# walktimizer_v2.net
KiCad netlist of a schematic drawn in Altium Designer
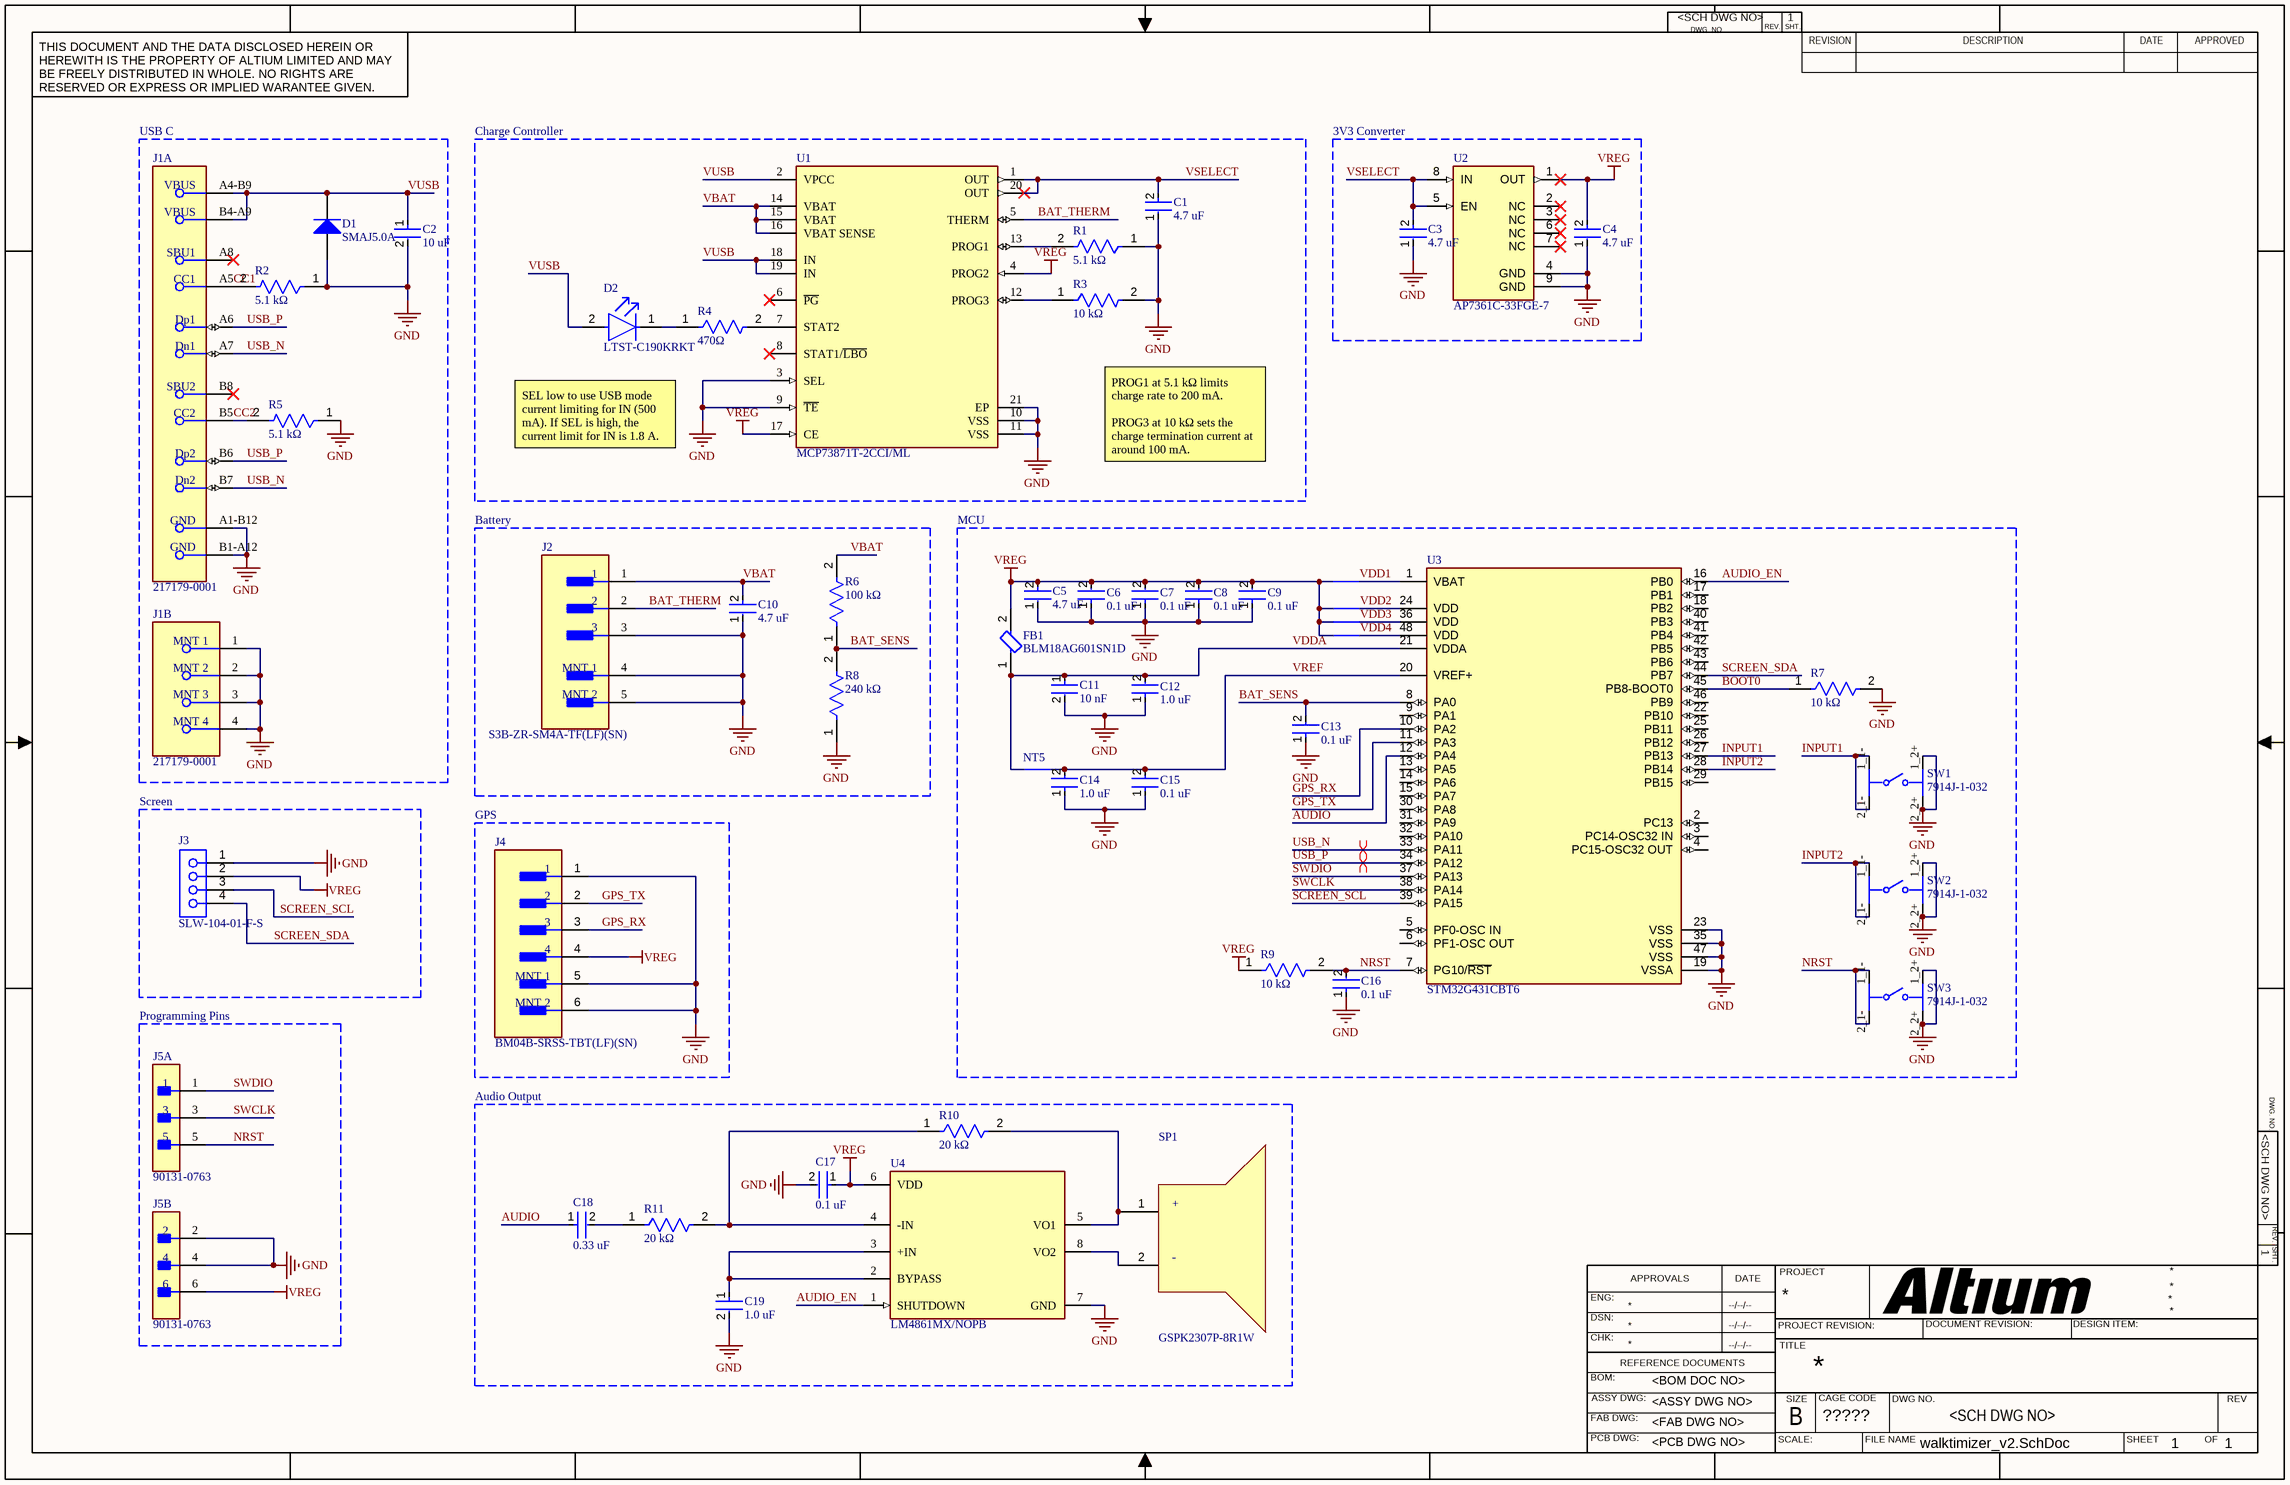
[diagram p0: walktimizer_v2.SchDoc]

(export (version "E")
  (design (tool "Eeschema 10.0.6"))
  (components
    (comp (ref "C1")
      (value "4.7 uF")
      (footprint "FP-GRM188-0_1-MFG")
      (description "CAP CER 4.7UF 6.3V X5R 0603\r\n\r\nGRM188R60J475KE19D")
      (fields (field (name "VOLTAGE") "6.3V") (field (name "TOLERANCE") "10%"))
      (libsource (lib "Altium Content Vault") (part "236180d848d6139a670b325ea6854c9"))
    )
    (comp (ref "C2")
      (value "10 uF")
      (footprint "FP-GRM21B-0_2-e0_2_0_7-IPC_A")
      (fields (field (name "TOLERANCE") "10%"))
      (libsource (lib "Altium Content Vault") (part "b4654b650e69147ec39a6b967a45e02"))
    )
    (comp (ref "C3")
      (value "4.7 uF")
      (footprint "FP-GRM188-0_1-MFG")
      (description "CAP CER 4.7UF 6.3V X5R 0603\r\n\r\nGRM188R60J475KE19D")
      (fields (field (name "VOLTAGE") "6.3V") (field (name "TOLERANCE") "10%"))
      (libsource (lib "Altium Content Vault") (part "236180d848d6139a670b325ea6854c9"))
    )
    (comp (ref "C4")
      (value "4.7 uF")
      (footprint "FP-GRM188-0_1-MFG")
      (description "CAP CER 4.7UF 6.3V X5R 0603\r\n\r\nGRM188R60J475KE19D")
      (fields (field (name "VOLTAGE") "6.3V") (field (name "TOLERANCE") "10%"))
      (libsource (lib "Altium Content Vault") (part "236180d848d6139a670b325ea6854c9"))
    )
    (comp (ref "C5")
      (value "4.7 uF")
      (footprint "FP-GRM188-0_1-MFG")
      (description "CAP CER 4.7UF 6.3V X5R 0603\r\n\r\nGRM188R60J475KE19D")
      (fields (field (name "VOLTAGE") "6.3V") (field (name "TOLERANCE") "10%"))
      (libsource (lib "Altium Content Vault") (part "236180d848d6139a670b325ea6854c9"))
    )
    (comp (ref "C6")
      (value "0.1 uF")
      (footprint "FP-CC0603-DA-MFG")
      (description "CAP CER 0.1UF 50V X7R 0603\r\n\r\nCC0603KRX7R9BB104")
      (fields (field (name "MANUFACTURER") "YAGEO") (field (name "VOLTAGE") "50 V"))
      (libsource (lib "Altium Content Vault") (part "11868f565c42a9108669ba33697ecf6"))
    )
    (comp (ref "C7")
      (value "0.1 uF")
      (footprint "FP-CC0603-DA-MFG")
      (description "CAP CER 0.1UF 50V X7R 0603\r\n\r\nCC0603KRX7R9BB104")
      (fields (field (name "MANUFACTURER") "YAGEO") (field (name "VOLTAGE") "50 V"))
      (libsource (lib "Altium Content Vault") (part "11868f565c42a9108669ba33697ecf6"))
    )
    (comp (ref "C8")
      (value "0.1 uF")
      (footprint "FP-CC0603-DA-MFG")
      (description "CAP CER 0.1UF 50V X7R 0603\r\n\r\nCC0603KRX7R9BB104")
      (fields (field (name "MANUFACTURER") "YAGEO") (field (name "VOLTAGE") "50 V"))
      (libsource (lib "Altium Content Vault") (part "11868f565c42a9108669ba33697ecf6"))
    )
    (comp (ref "C9")
      (value "0.1 uF")
      (footprint "FP-CC0603-DA-MFG")
      (description "CAP CER 0.1UF 50V X7R 0603\r\n\r\nCC0603KRX7R9BB104")
      (fields (field (name "MANUFACTURER") "YAGEO") (field (name "VOLTAGE") "50 V"))
      (libsource (lib "Altium Content Vault") (part "11868f565c42a9108669ba33697ecf6"))
    )
    (comp (ref "C10")
      (value "4.7 uF")
      (footprint "FP-GRM188-0_1-MFG")
      (description "CAP CER 4.7UF 6.3V X5R 0603\r\n\r\nGRM188R60J475KE19D")
      (fields (field (name "VOLTAGE") "6.3V") (field (name "TOLERANCE") "10%"))
      (libsource (lib "Altium Content Vault") (part "236180d848d6139a670b325ea6854c9"))
    )
    (comp (ref "C11")
      (value "10 nF")
      (footprint "FP-CC0603-DA-MFG")
      (description "CAP CER 10000PF 50V X7R 0603\r\n\r\nCC0603KRX7R9BB103")
      (fields (field (name "TOLERANCE") "0.1") (field (name "MANUFACTURER PART NUMBER") "CC0603KRX7R9BB103"))
      (libsource (lib "Altium Content Vault") (part "11868f565c42a9108669ba33697ecf6"))
    )
    (comp (ref "C12")
      (value "1.0 uF")
      (footprint "FP-CC0603-DB-MFG")
      (description "CAP CER 1UF 50V X7R 0603\r\n\r\nCC0603KRX7R9BB105")
      (fields (field (name "TOLERANCE") "10%"))
      (libsource (lib "Altium Content Vault") (part "11868f565c42a9108669ba33697ecf6"))
    )
    (comp (ref "C13")
      (value "0.1 uF")
      (footprint "FP-CC0603-DA-MFG")
      (description "CAP CER 0.1UF 50V X7R 0603\r\n\r\nCC0603KRX7R9BB104")
      (fields (field (name "MANUFACTURER") "YAGEO") (field (name "VOLTAGE") "50 V"))
      (libsource (lib "Altium Content Vault") (part "11868f565c42a9108669ba33697ecf6"))
    )
    (comp (ref "C14")
      (value "1.0 uF")
      (footprint "FP-CC0603-DB-MFG")
      (description "CAP CER 1UF 50V X7R 0603\r\n\r\nCC0603KRX7R9BB105")
      (fields (field (name "TOLERANCE") "10%"))
      (libsource (lib "Altium Content Vault") (part "11868f565c42a9108669ba33697ecf6"))
    )
    (comp (ref "C15")
      (value "0.1 uF")
      (footprint "FP-CC0603-DA-MFG")
      (description "CAP CER 0.1UF 50V X7R 0603\r\n\r\nCC0603KRX7R9BB104")
      (fields (field (name "MANUFACTURER") "YAGEO") (field (name "VOLTAGE") "50 V"))
      (libsource (lib "Altium Content Vault") (part "11868f565c42a9108669ba33697ecf6"))
    )
    (comp (ref "C16")
      (value "0.1 uF")
      (footprint "FP-CC0603-DA-MFG")
      (description "CAP CER 0.1UF 50V X7R 0603\r\n\r\nCC0603KRX7R9BB104")
      (fields (field (name "MANUFACTURER") "YAGEO") (field (name "VOLTAGE") "50 V"))
      (libsource (lib "Altium Content Vault") (part "11868f565c42a9108669ba33697ecf6"))
    )
    (comp (ref "C17")
      (value "0.1 uF")
      (footprint "FP-CC0603-DA-MFG")
      (description "CAP CER 0.1UF 50V X7R 0603\r\n\r\nCC0603KRX7R9BB104")
      (fields (field (name "MANUFACTURER") "YAGEO") (field (name "VOLTAGE") "50 V"))
      (libsource (lib "Altium Content Vault") (part "11868f565c42a9108669ba33697ecf6"))
    )
    (comp (ref "C18")
      (value "0.33 uF")
      (footprint "FP-CC0603-DA-MFG")
      (description "CAP CER 0.33UF 25V X7R 0603\r\n\r\nCC0603KRX7R8BB334")
      (fields
        (field (name "VOLTAGE") "25 V")
        (field (name "OCTOPART") "https://octopart.com/cc0603krx7r8bb334-yageo-47255252")
      )
      (libsource (lib "Altium Content Vault") (part "11868f565c42a9108669ba33697ecf6"))
    )
    (comp (ref "C19")
      (value "1.0 uF")
      (footprint "FP-CC0603-DB-MFG")
      (description "CAP CER 1UF 50V X7R 0603\r\n\r\nCC0603KRX7R9BB105")
      (fields (field (name "TOLERANCE") "10%"))
      (libsource (lib "Altium Content Vault") (part "11868f565c42a9108669ba33697ecf6"))
    )
    (comp (ref "D1")
      (value "SMAJ5.0A")
      (footprint "BOUR-SMA-2_V")
      (fields (field (name "MANUFACTURER") "Bourns"))
      (libsource (lib "Altium Content Vault") (part "D-AK-2"))
    )
    (comp (ref "D2")
      (value "LTST-C190KRKT")
      (footprint "FP-LTST-C190KRKT-MFG")
      (description "LED RED CLEAR CHIP SMD")
      (libsource (lib "Altium Content Vault") (part "8706943c75ba83719d021d2fdc84c58"))
    )
    (comp (ref "FB1")
      (value "BLM18AG601SN1D")
      (footprint "FP-BLM18-0_15-t0_8-MFG")
      (description "Chip Ferrite Bead, 0603, 600Ω @ 100MHz, 0.38Ω, 25%, 500mA")
      (fields (field (name "TOLERANCE") "25%"))
      (libsource (lib "Altium Content Vault") (part "5f30dd21d616792df468990f7003faa"))
    )
    (comp (ref "J1")
      (value "217179-0001")
      (footprint "FP-2171790001-MFG")
      (description "CONN RCP USB2.0 TYP C 24P SMD RA")
      (libsource (lib "Altium Content Vault") (part "8b86497a633d14b3f74642136fc0ce6"))
    )
    (comp (ref "J2")
      (value "S3B-ZR-SM4A-TF(LF)(SN)")
      (footprint "FP-S3B-ZR-SM4A-TF_LF_SN-MFG")
      (description "CONN HEADER SMD R/A 3POS 1.5MM")
      (libsource (lib "Altium Content Vault") (part "38689d6f3df0f9b234c6ddcef280d85"))
    )
    (comp (ref "J3")
      (value "SLW-104-01-F-S")
      (footprint "SMTC-SLW-104-01-X-S")
      (fields (field (name "MANUFACTURER") "Samtec"))
      (libsource (lib "Altium Content Vault") (part "SMTC-SLW-104-01-X-S"))
    )
    (comp (ref "J4")
      (value "BM04B-SRSS-TBT(LF)(SN)")
      (footprint "FP-BM04B-SRSS-TBT_LF_SN-MFG")
      (description "CONN HEADER SMD 4POS 1MM")
      (libsource (lib "Altium Content Vault") (part "8e3688c4b118bffc0dd9b7401e414ba"))
    )
    (comp (ref "J5")
      (value "90131-0763")
      (footprint "FP-90131-0763-MFG")
      (description "90131-0763 Conn Unshrouded Header HDR 6 POS 2.54mm Solder ST Top Entry Thru-Hole C-Grid III™ Tray")
      (libsource (lib "Altium Content Vault") (part "2654a11fb13586ecb194516b1c997bc"))
    )
    (comp (ref "NT1")
      (value "NT")
      (footprint "NETTIE_SMD")
      (description "Net Tie SMD")
      (libsource (lib "Schlib1") (part "NetTie_SMD"))
    )
    (comp (ref "NT2")
      (value "NT")
      (footprint "NETTIE_SMD")
      (description "Net Tie SMD")
      (libsource (lib "Schlib1") (part "NetTie_SMD"))
    )
    (comp (ref "NT3")
      (value "NT")
      (footprint "NETTIE_SMD")
      (description "Net Tie SMD")
      (libsource (lib "Schlib1") (part "NetTie_SMD"))
    )
    (comp (ref "NT4")
      (value "NT")
      (footprint "NETTIE_SMD")
      (description "Net Tie SMD")
      (libsource (lib "Schlib1") (part "NetTie_SMD"))
    )
    (comp (ref "NT5")
      (value "NT")
      (footprint "NETTIE_SMD")
      (description "Net Tie SMD")
      (libsource (lib "Schlib1") (part "NetTie_SMD"))
    )
    (comp (ref "R1")
      (value "5.1 kΩ")
      (footprint "FP-CRCW0603-e3-IPC_C")
      (description "RES Thick Film, 5.1kΩ, 1%, 0.1W, 100ppm/°C, 0603\r\n\r\nCRCW06035K10FKEA")
      (fields (field (name "TOLERANCE") "1%"))
      (libsource (lib "Altium Content Vault") (part "1029c3af85768c4190bb7ad29bc67b5"))
    )
    (comp (ref "R2")
      (value "5.1 kΩ")
      (footprint "FP-CRCW0603-e3-IPC_C")
      (description "RES Thick Film, 5.1kΩ, 1%, 0.1W, 100ppm/°C, 0603\r\n\r\nCRCW06035K10FKEA")
      (fields (field (name "TOLERANCE") "1%"))
      (libsource (lib "Altium Content Vault") (part "1029c3af85768c4190bb7ad29bc67b5"))
    )
    (comp (ref "R3")
      (value "10 kΩ")
      (footprint "FP-RC0603-0_55-IPC_C")
      (description "RES 10kΩ 1% 1/10W 0603\r\n\r\nRC0603FR-0710KL")
      (fields (field (name "TOLERANCE") "1%"))
      (libsource (lib "Altium Content Vault") (part "1029c3af85768c4190bb7ad29bc67b5"))
    )
    (comp (ref "R4")
      (value "470Ω")
      (footprint "FP-CRCW0603-e3-MFG")
      (description "RES Thick Film, 470Ω, 1%, 0.1W, 100ppm/°C, 0603\r\n\r\nCRCW0603470RFKEA")
      (fields (field (name "TOLERANCE") "1%"))
      (libsource (lib "Altium Content Vault") (part "1029c3af85768c4190bb7ad29bc67b5"))
    )
    (comp (ref "R5")
      (value "5.1 kΩ")
      (footprint "FP-CRCW0603-e3-IPC_C")
      (description "RES Thick Film, 5.1kΩ, 1%, 0.1W, 100ppm/°C, 0603\r\n\r\nCRCW06035K10FKEA")
      (fields (field (name "TOLERANCE") "1%"))
      (libsource (lib "Altium Content Vault") (part "1029c3af85768c4190bb7ad29bc67b5"))
    )
    (comp (ref "R6")
      (value "100 kΩ")
      (footprint "FP-RC0603-0_55-MFG")
      (description "RES SMD 100K OHM 1% 1/10W 0603\r\n\r\nRC0603FR-07100KL")
      (fields (field (name "TOLERANCE") "1%"))
      (libsource (lib "Altium Content Vault") (part "1029c3af85768c4190bb7ad29bc67b5"))
    )
    (comp (ref "R7")
      (value "10 kΩ")
      (footprint "FP-RC0603-0_55-IPC_C")
      (description "RES 10kΩ 1% 1/10W 0603\r\n\r\nRC0603FR-0710KL")
      (fields (field (name "TOLERANCE") "1%"))
      (libsource (lib "Altium Content Vault") (part "1029c3af85768c4190bb7ad29bc67b5"))
    )
    (comp (ref "R8")
      (value "240 kΩ")
      (footprint "FP-RT0603-MFG")
      (description "RES 240K OHM 1/10W .1% SMD 0603\r\n\r\nRT0603BRD07240KL")
      (fields
        (field (name "OCTOPART") "https://octopart.com/rt0603brd07240kl-yageo-1283207")
        (field (name "TOLERANCE") "0.001")
      )
      (libsource (lib "Altium Content Vault") (part "1029c3af85768c4190bb7ad29bc67b5"))
    )
    (comp (ref "R9")
      (value "10 kΩ")
      (footprint "FP-RC0603-0_55-IPC_C")
      (description "RES 10kΩ 1% 1/10W 0603\r\n\r\nRC0603FR-0710KL")
      (fields (field (name "TOLERANCE") "1%"))
      (libsource (lib "Altium Content Vault") (part "1029c3af85768c4190bb7ad29bc67b5"))
    )
    (comp (ref "R10")
      (value "20 kΩ")
      (footprint "FP-RC0603-0_55-IPC_C")
      (description "RES 20K OHM 1% 1/10W 0603\r\n\r\nRC0603FR-0720KL")
      (fields (field (name "TOLERANCE") "1%"))
      (libsource (lib "Altium Content Vault") (part "1029c3af85768c4190bb7ad29bc67b5"))
    )
    (comp (ref "R11")
      (value "20 kΩ")
      (footprint "FP-RC0603-0_55-IPC_C")
      (description "RES 20K OHM 1% 1/10W 0603\r\n\r\nRC0603FR-0720KL")
      (fields (field (name "TOLERANCE") "1%"))
      (libsource (lib "Altium Content Vault") (part "1029c3af85768c4190bb7ad29bc67b5"))
    )
    (comp (ref "SP1")
      (value "GSPK2307P-8R1W")
      (footprint "GSPK2307P-8R1W-Footprint-1")
      (description "8 ohm 1.7kHz Speakers ROHS 88dB 500 mW")
      (libsource (lib "Americas - University of Calgary - Schulich Unmanned Aerial Vehicle (SUAV)") (part "GSPK2307P-8R1W-Symbol-1"))
    )
    (comp (ref "SW1")
      (value "7914J-1-032")
      (footprint "FP-7914J-1-032-MFG")
      (description "SWITCH TACTILE SPST-NO 0.1A 16V")
      (libsource (lib "Altium Content Vault") (part "31b61e1575766857d5d37af9ed38f2e"))
    )
    (comp (ref "SW2")
      (value "7914J-1-032")
      (footprint "FP-7914J-1-032-MFG")
      (description "SWITCH TACTILE SPST-NO 0.1A 16V")
      (libsource (lib "Altium Content Vault") (part "31b61e1575766857d5d37af9ed38f2e"))
    )
    (comp (ref "SW3")
      (value "7914J-1-032")
      (footprint "FP-7914J-1-032-MFG")
      (description "SWITCH TACTILE SPST-NO 0.1A 16V")
      (libsource (lib "Altium Content Vault") (part "31b61e1575766857d5d37af9ed38f2e"))
    )
    (comp (ref "U1")
      (value "MCP73871T-2CCI/ML")
      (footprint "FP-C04-126-IPC_C")
      (description "IC USB/AC BATT CHRGR W/PPM 20QFN")
      (libsource (lib "Altium Content Vault") (part "b0f216601a400a2976e0698385bc2c7"))
    )
    (comp (ref "U2")
      (value "AP7361C-33FGE-7")
      (footprint "FP-U-DFN3030-8_Type_E-MFG")
      (description "IC REG LINEAR 3.3V 1A UDFN3030-8")
      (fields
        (field (name "MANUFACTURER") "Diodes Inc.")
        (field (name "OCTOPART") "https://octopart.com/ap7361c-33fge-7-diodes+inc.-65869522")
      )
      (libsource (lib "Altium Content Vault") (part "2971fe8480f7e8815ea3c3920f93e3e"))
    )
    (comp (ref "U3")
      (value "STM32G431CBT6")
      (footprint "FP-LQFP48-5B-MFG")
      (description "MAINSTREAM ARM CORTEX-M4+ MCU 17")
      (fields
        (field (name "MANUFACTURER") "STMicroelectronics")
        (field (name "OCTOPART") "https://octopart.com/stm32g431cbt6-stmicroelectronics-98835224")
      )
      (libsource (lib "Altium Content Vault") (part "08b09c1d51ec08ade740842f2b8671b"))
    )
    (comp (ref "U4")
      (value "LM4861MX/NOPB")
      (footprint "FP-D0008A-MFG")
      (description "IC AMP CLASS AB MONO 1.5W 8SOIC")
      (libsource (lib "Altium Content Vault") (part "2ffc3cc6e4eb487d9499d4bad086ba9"))
    )
  )
  (nets
    (net (code "1") (name "/AUDIO") (class "Default")
      (node (ref "C18") (pin "1") (pinfunction "1_1") (pintype "passive"))
      (node (ref "U3") (pin "12") (pinfunction "PA4_12") (pintype "bidirectional"))
    )
    (net (code "2") (name "/AUDIO_EN") (class "Default")
      (node (ref "U3") (pin "16") (pinfunction "PB0_16") (pintype "bidirectional"))
      (node (ref "U4") (pin "1") (pinfunction "SHUTDOWN_1") (pintype "input"))
    )
    (net (code "3") (name "/BAT_SENS") (class "Default")
      (node (ref "C13") (pin "2") (pinfunction "2_2") (pintype "passive"))
      (node (ref "R6") (pin "1") (pinfunction "1_1") (pintype "passive"))
      (node (ref "R8") (pin "2") (pinfunction "2_2") (pintype "passive"))
      (node (ref "U3") (pin "8") (pinfunction "PA0_8") (pintype "bidirectional"))
    )
    (net (code "4") (name "/BAT_THERM") (class "Default")
      (node (ref "J2") (pin "2") (pinfunction "2_2") (pintype "passive"))
      (node (ref "U1") (pin "5") (pinfunction "THERM_5") (pintype "bidirectional"))
    )
    (net (code "5") (name "/BOOT0") (class "Default")
      (node (ref "R7") (pin "1") (pinfunction "1_1") (pintype "passive"))
      (node (ref "U3") (pin "45") (pinfunction "PB8-BOOT0_45") (pintype "bidirectional"))
    )
    (net (code "6") (name "/CC1") (class "Default")
      (node (ref "J1") (pin "A5") (pinfunction "CC1_A5") (pintype "passive"))
      (node (ref "R2") (pin "2") (pinfunction "2_2") (pintype "passive"))
    )
    (net (code "7") (name "/CC2") (class "Default")
      (node (ref "J1") (pin "B5") (pinfunction "CC2_B5") (pintype "passive"))
      (node (ref "R5") (pin "2") (pinfunction "2_2") (pintype "passive"))
    )
    (net (code "8") (name "/GPS_RX") (class "Default")
      (node (ref "J4") (pin "3") (pinfunction "3_3") (pintype "passive"))
      (node (ref "U3") (pin "10") (pinfunction "PA2_10") (pintype "bidirectional"))
    )
    (net (code "9") (name "/GPS_TX") (class "Default")
      (node (ref "J4") (pin "2") (pinfunction "2_2") (pintype "passive"))
      (node (ref "U3") (pin "11") (pinfunction "PA3_11") (pintype "bidirectional"))
    )
    (net (code "10") (name "/INPUT1") (class "Default")
      (node (ref "SW1") (pin "1_1-") (pinfunction "1_1-_1_1-") (pintype "passive"))
      (node (ref "SW1") (pin "2_1-") (pinfunction "2_1-_2_1-") (pintype "passive"))
      (node (ref "U3") (pin "27") (pinfunction "PB13_27") (pintype "bidirectional"))
    )
    (net (code "11") (name "/INPUT2") (class "Default")
      (node (ref "SW2") (pin "1_1-") (pinfunction "1_1-_1_1-") (pintype "passive"))
      (node (ref "SW2") (pin "2_1-") (pinfunction "2_1-_2_1-") (pintype "passive"))
      (node (ref "U3") (pin "28") (pinfunction "PB14_28") (pintype "bidirectional"))
    )
    (net (code "12") (name "/NRST") (class "Default")
      (node (ref "C16") (pin "2") (pinfunction "2_2") (pintype "passive"))
      (node (ref "J5") (pin "5") (pinfunction "5_5") (pintype "passive"))
      (node (ref "R9") (pin "2") (pinfunction "2_2") (pintype "passive"))
      (node (ref "SW3") (pin "1_1-") (pinfunction "1_1-_1_1-") (pintype "passive"))
      (node (ref "SW3") (pin "2_1-") (pinfunction "2_1-_2_1-") (pintype "passive"))
      (node (ref "U3") (pin "7") (pinfunction "PG10/~{RST}_7") (pintype "bidirectional"))
    )
    (net (code "13") (name "/SCREEN_SCL") (class "Default")
      (node (ref "J3") (pin "3") (pinfunction "3_3") (pintype "passive"))
      (node (ref "U3") (pin "39") (pinfunction "PA15_39") (pintype "bidirectional"))
    )
    (net (code "14") (name "/SCREEN_SDA") (class "Default")
      (node (ref "J3") (pin "4") (pinfunction "4_4") (pintype "passive"))
      (node (ref "U3") (pin "44") (pinfunction "PB7_44") (pintype "bidirectional"))
    )
    (net (code "15") (name "/SWCLK") (class "Default")
      (node (ref "J5") (pin "3") (pinfunction "3_3") (pintype "passive"))
      (node (ref "U3") (pin "38") (pinfunction "PA14_38") (pintype "bidirectional"))
    )
    (net (code "16") (name "/SWDIO") (class "Default")
      (node (ref "J5") (pin "1") (pinfunction "1_1") (pintype "passive"))
      (node (ref "U3") (pin "37") (pinfunction "PA13_37") (pintype "bidirectional"))
    )
    (net (code "17") (name "/USB_N") (class "Default")
      (node (ref "J1") (pin "A7") (pinfunction "Dn1_A7") (pintype "bidirectional"))
      (node (ref "J1") (pin "B7") (pinfunction "Dn2_B7") (pintype "bidirectional"))
      (node (ref "U3") (pin "33") (pinfunction "PA11_33") (pintype "bidirectional"))
    )
    (net (code "18") (name "/USB_P") (class "Default")
      (node (ref "J1") (pin "A6") (pinfunction "Dp1_A6") (pintype "bidirectional"))
      (node (ref "J1") (pin "B6") (pinfunction "Dp2_B6") (pintype "bidirectional"))
      (node (ref "U3") (pin "34") (pinfunction "PA12_34") (pintype "bidirectional"))
    )
    (net (code "19") (name "/VBAT") (class "Default")
      (node (ref "C10") (pin "2") (pinfunction "2_2") (pintype "passive"))
      (node (ref "J2") (pin "1") (pinfunction "1_1") (pintype "passive"))
      (node (ref "R6") (pin "2") (pinfunction "2_2") (pintype "passive"))
      (node (ref "U1") (pin "14") (pinfunction "VBAT_14") (pintype "power_in"))
      (node (ref "U1") (pin "15") (pinfunction "VBAT_15") (pintype "power_in"))
      (node (ref "U1") (pin "16") (pinfunction "VBAT_SENSE_16") (pintype "power_in"))
    )
    (net (code "20") (name "/VDD1") (class "Default")
      (node (ref "NT1") (pin "2") (pinfunction "2_2") (pintype "passive"))
      (node (ref "U3") (pin "1") (pinfunction "VBAT_1") (pintype "power_in"))
    )
    (net (code "21") (name "/VDD2") (class "Default")
      (node (ref "NT2") (pin "2") (pinfunction "2_2") (pintype "passive"))
      (node (ref "U3") (pin "24") (pinfunction "VDD_24") (pintype "power_in"))
    )
    (net (code "22") (name "/VDD3") (class "Default")
      (node (ref "NT3") (pin "2") (pinfunction "2_2") (pintype "passive"))
      (node (ref "U3") (pin "36") (pinfunction "VDD_36") (pintype "power_in"))
    )
    (net (code "23") (name "/VDD4") (class "Default")
      (node (ref "NT4") (pin "2") (pinfunction "2_2") (pintype "passive"))
      (node (ref "U3") (pin "48") (pinfunction "VDD_48") (pintype "power_in"))
    )
    (net (code "24") (name "/VDDA") (class "Default")
      (node (ref "C11") (pin "1") (pinfunction "1_1") (pintype "passive"))
      (node (ref "C12") (pin "2") (pinfunction "2_2") (pintype "passive"))
      (node (ref "FB1") (pin "1") (pinfunction "1_1") (pintype "passive"))
      (node (ref "NT5") (pin "1") (pinfunction "1_1") (pintype "passive"))
      (node (ref "U3") (pin "21") (pinfunction "VDDA_21") (pintype "power_in"))
    )
    (net (code "25") (name "/VREF") (class "Default")
      (node (ref "C14") (pin "2") (pinfunction "2_2") (pintype "passive"))
      (node (ref "C15") (pin "2") (pinfunction "2_2") (pintype "passive"))
      (node (ref "NT5") (pin "2") (pinfunction "2_2") (pintype "passive"))
      (node (ref "U3") (pin "20") (pinfunction "VREF+_20") (pintype "power_in"))
    )
    (net (code "26") (name "/VSELECT") (class "Default")
      (node (ref "C1") (pin "2") (pinfunction "2_2") (pintype "passive"))
      (node (ref "C3") (pin "2") (pinfunction "2_2") (pintype "passive"))
      (node (ref "U1") (pin "1") (pinfunction "OUT_1") (pintype "output"))
      (node (ref "U1") (pin "20") (pinfunction "OUT_20") (pintype "output"))
      (node (ref "U2") (pin "5") (pinfunction "EN_5") (pintype "input"))
      (node (ref "U2") (pin "8") (pinfunction "IN_8") (pintype "input"))
    )
    (net (code "27") (name "/VUSB") (class "Default")
      (node (ref "C2") (pin "1") (pinfunction "1_1") (pintype "passive"))
      (node (ref "D1") (pin "2") (pinfunction "K_2") (pintype "passive"))
      (node (ref "D2") (pin "2") (pinfunction "A_2") (pintype "passive"))
      (node (ref "J1") (pin "A4-B9") (pinfunction "VBUS_A4-B9") (pintype "power_in"))
      (node (ref "J1") (pin "B4-A9") (pinfunction "VBUS_B4-A9") (pintype "power_in"))
      (node (ref "U1") (pin "18") (pinfunction "IN_18") (pintype "power_in"))
      (node (ref "U1") (pin "19") (pinfunction "IN_19") (pintype "power_in"))
      (node (ref "U1") (pin "2") (pinfunction "VPCC_2") (pintype "power_in"))
    )
    (net (code "28") (name "GND") (class "Default")
      (node (ref "C1") (pin "1") (pinfunction "1_1") (pintype "passive"))
      (node (ref "C10") (pin "1") (pinfunction "1_1") (pintype "passive"))
      (node (ref "C11") (pin "2") (pinfunction "2_2") (pintype "passive"))
      (node (ref "C12") (pin "1") (pinfunction "1_1") (pintype "passive"))
      (node (ref "C13") (pin "1") (pinfunction "1_1") (pintype "passive"))
      (node (ref "C14") (pin "1") (pinfunction "1_1") (pintype "passive"))
      (node (ref "C15") (pin "1") (pinfunction "1_1") (pintype "passive"))
      (node (ref "C16") (pin "1") (pinfunction "1_1") (pintype "passive"))
      (node (ref "C17") (pin "2") (pinfunction "2_2") (pintype "passive"))
      (node (ref "C19") (pin "2") (pinfunction "2_2") (pintype "passive"))
      (node (ref "C2") (pin "2") (pinfunction "2_2") (pintype "passive"))
      (node (ref "C3") (pin "1") (pinfunction "1_1") (pintype "passive"))
      (node (ref "C4") (pin "1") (pinfunction "1_1") (pintype "passive"))
      (node (ref "C5") (pin "1") (pinfunction "1_1") (pintype "passive"))
      (node (ref "C6") (pin "1") (pinfunction "1_1") (pintype "passive"))
      (node (ref "C7") (pin "1") (pinfunction "1_1") (pintype "passive"))
      (node (ref "C8") (pin "1") (pinfunction "1_1") (pintype "passive"))
      (node (ref "C9") (pin "1") (pinfunction "1_1") (pintype "passive"))
      (node (ref "D1") (pin "1") (pinfunction "A_1") (pintype "passive"))
      (node (ref "J1") (pin "1") (pinfunction "MNT_1_1") (pintype "passive"))
      (node (ref "J1") (pin "2") (pinfunction "MNT_2_2") (pintype "passive"))
      (node (ref "J1") (pin "3") (pinfunction "MNT_3_3") (pintype "power_in"))
      (node (ref "J1") (pin "4") (pinfunction "MNT_4_4") (pintype "power_in"))
      (node (ref "J1") (pin "A1-B12") (pinfunction "GND_A1-B12") (pintype "power_in"))
      (node (ref "J1") (pin "B1-A12") (pinfunction "GND_B1-A12") (pintype "power_in"))
      (node (ref "J2") (pin "3") (pinfunction "3_3") (pintype "passive"))
      (node (ref "J2") (pin "4") (pinfunction "MNT_1_4") (pintype "passive"))
      (node (ref "J2") (pin "5") (pinfunction "MNT_2_5") (pintype "passive"))
      (node (ref "J3") (pin "1") (pinfunction "1_1") (pintype "passive"))
      (node (ref "J4") (pin "1") (pinfunction "1_1") (pintype "passive"))
      (node (ref "J4") (pin "5") (pinfunction "MNT_1_5") (pintype "passive"))
      (node (ref "J4") (pin "6") (pinfunction "MNT_2_6") (pintype "passive"))
      (node (ref "J5") (pin "2") (pinfunction "2_2") (pintype "passive"))
      (node (ref "J5") (pin "4") (pinfunction "4_4") (pintype "passive"))
      (node (ref "R1") (pin "1") (pinfunction "1_1") (pintype "passive"))
      (node (ref "R2") (pin "1") (pinfunction "1_1") (pintype "passive"))
      (node (ref "R3") (pin "2") (pinfunction "2_2") (pintype "passive"))
      (node (ref "R5") (pin "1") (pinfunction "1_1") (pintype "passive"))
      (node (ref "R7") (pin "2") (pinfunction "2_2") (pintype "passive"))
      (node (ref "R8") (pin "1") (pinfunction "1_1") (pintype "passive"))
      (node (ref "SW1") (pin "1_2+") (pinfunction "1_2+_1_2+") (pintype "passive"))
      (node (ref "SW1") (pin "2_2+") (pinfunction "2_2+_2_2+") (pintype "passive"))
      (node (ref "SW2") (pin "1_2+") (pinfunction "1_2+_1_2+") (pintype "passive"))
      (node (ref "SW2") (pin "2_2+") (pinfunction "2_2+_2_2+") (pintype "passive"))
      (node (ref "SW3") (pin "1_2+") (pinfunction "1_2+_1_2+") (pintype "passive"))
      (node (ref "SW3") (pin "2_2+") (pinfunction "2_2+_2_2+") (pintype "passive"))
      (node (ref "U1") (pin "10") (pinfunction "VSS_10") (pintype "power_in"))
      (node (ref "U1") (pin "11") (pinfunction "VSS_11") (pintype "power_in"))
      (node (ref "U1") (pin "21") (pinfunction "EP_21") (pintype "passive"))
      (node (ref "U1") (pin "3") (pinfunction "SEL_3") (pintype "input"))
      (node (ref "U1") (pin "9") (pinfunction "~{TE}_9") (pintype "input"))
      (node (ref "U2") (pin "4") (pinfunction "GND_4") (pintype "power_in"))
      (node (ref "U2") (pin "9") (pinfunction "GND_9") (pintype "power_in"))
      (node (ref "U3") (pin "19") (pinfunction "VSSA_19") (pintype "power_in"))
      (node (ref "U3") (pin "23") (pinfunction "VSS_23") (pintype "power_in"))
      (node (ref "U3") (pin "35") (pinfunction "VSS_35") (pintype "power_in"))
      (node (ref "U3") (pin "47") (pinfunction "VSS_47") (pintype "power_in"))
      (node (ref "U4") (pin "7") (pinfunction "GND_7") (pintype "power_in"))
    )
    (net (code "29") (name "Net-(C18-Pad2)") (class "Default")
      (node (ref "C18") (pin "2") (pinfunction "2_2") (pintype "passive"))
      (node (ref "R11") (pin "1") (pinfunction "1_1") (pintype "passive"))
    )
    (net (code "30") (name "Net-(D2-C)") (class "Default")
      (node (ref "D2") (pin "1") (pinfunction "C_1") (pintype "passive"))
      (node (ref "R4") (pin "1") (pinfunction "1_1") (pintype "passive"))
    )
    (net (code "31") (name "Net-(U1-PROG1)") (class "Default")
      (node (ref "R1") (pin "2") (pinfunction "2_2") (pintype "passive"))
      (node (ref "U1") (pin "13") (pinfunction "PROG1_13") (pintype "bidirectional"))
    )
    (net (code "32") (name "Net-(U1-PROG3)") (class "Default")
      (node (ref "R3") (pin "1") (pinfunction "1_1") (pintype "passive"))
      (node (ref "U1") (pin "12") (pinfunction "PROG3_12") (pintype "bidirectional"))
    )
    (net (code "33") (name "Net-(U1-STAT2)") (class "Default")
      (node (ref "R4") (pin "2") (pinfunction "2_2") (pintype "passive"))
      (node (ref "U1") (pin "7") (pinfunction "STAT2_7") (pintype "open_collector"))
    )
    (net (code "34") (name "Net-(U4-+IN)") (class "Default")
      (node (ref "C19") (pin "1") (pinfunction "1_1") (pintype "passive"))
      (node (ref "U4") (pin "2") (pinfunction "BYPASS_2") (pintype "passive"))
      (node (ref "U4") (pin "3") (pinfunction "+IN_3") (pintype "tri_state"))
    )
    (net (code "35") (name "Net-(U4--IN)") (class "Default")
      (node (ref "R10") (pin "1") (pinfunction "1_1") (pintype "passive"))
      (node (ref "R11") (pin "2") (pinfunction "2_2") (pintype "passive"))
      (node (ref "U4") (pin "4") (pinfunction "-IN_4") (pintype "tri_state"))
    )
    (net (code "36") (name "Net-(U4-VO1)") (class "Default")
      (node (ref "R10") (pin "2") (pinfunction "2_2") (pintype "passive"))
      (node (ref "SP1") (pin "1") (pinfunction "1_1") (pintype "passive"))
      (node (ref "U4") (pin "5") (pinfunction "VO1_5") (pintype "passive"))
    )
    (net (code "37") (name "Net-(U4-VO2)") (class "Default")
      (node (ref "SP1") (pin "2") (pinfunction "2_2") (pintype "passive"))
      (node (ref "U4") (pin "8") (pinfunction "VO2_8") (pintype "passive"))
    )
    (net (code "38") (name "VREG") (class "Default")
      (node (ref "C17") (pin "1") (pinfunction "1_1") (pintype "passive"))
      (node (ref "C4") (pin "2") (pinfunction "2_2") (pintype "passive"))
      (node (ref "C5") (pin "2") (pinfunction "2_2") (pintype "passive"))
      (node (ref "C6") (pin "2") (pinfunction "2_2") (pintype "passive"))
      (node (ref "C7") (pin "2") (pinfunction "2_2") (pintype "passive"))
      (node (ref "C8") (pin "2") (pinfunction "2_2") (pintype "passive"))
      (node (ref "C9") (pin "2") (pinfunction "2_2") (pintype "passive"))
      (node (ref "FB1") (pin "2") (pinfunction "2_2") (pintype "passive"))
      (node (ref "J3") (pin "2") (pinfunction "2_2") (pintype "passive"))
      (node (ref "J4") (pin "4") (pinfunction "4_4") (pintype "passive"))
      (node (ref "J5") (pin "6") (pinfunction "6_6") (pintype "passive"))
      (node (ref "NT1") (pin "1") (pinfunction "1_1") (pintype "passive"))
      (node (ref "NT2") (pin "1") (pinfunction "1_1") (pintype "passive"))
      (node (ref "NT3") (pin "1") (pinfunction "1_1") (pintype "passive"))
      (node (ref "NT4") (pin "1") (pinfunction "1_1") (pintype "passive"))
      (node (ref "R9") (pin "1") (pinfunction "1_1") (pintype "passive"))
      (node (ref "U1") (pin "17") (pinfunction "CE_17") (pintype "input"))
      (node (ref "U1") (pin "4") (pinfunction "PROG2_4") (pintype "input"))
      (node (ref "U2") (pin "1") (pinfunction "OUT_1") (pintype "output"))
      (node (ref "U4") (pin "6") (pinfunction "VDD_6") (pintype "power_in"))
    )
    (net (code "39") (name "unconnected-(J1A-SBU1-PadA8)") (class "Default")
      (node (ref "J1") (pin "A8") (pinfunction "SBU1_A8") (pintype "passive+no_connect"))
    )
    (net (code "40") (name "unconnected-(J1A-SBU2-PadB8)") (class "Default")
      (node (ref "J1") (pin "B8") (pinfunction "SBU2_B8") (pintype "passive+no_connect"))
    )
    (net (code "41") (name "unconnected-(U1-STAT1{slash}~{LBO}-Pad8)") (class "Default")
      (node (ref "U1") (pin "8") (pinfunction "STAT1/~{LBO}_8") (pintype "open_collector+no_connect"))
    )
    (net (code "42") (name "unconnected-(U1-~{PG}-Pad6)") (class "Default")
      (node (ref "U1") (pin "6") (pinfunction "~{PG}_6") (pintype "open_collector+no_connect"))
    )
    (net (code "43") (name "unconnected-(U2-NC-Pad2)") (class "Default")
      (node (ref "U2") (pin "2") (pinfunction "NC_2") (pintype "passive+no_connect"))
    )
    (net (code "44") (name "unconnected-(U2-NC-Pad3)") (class "Default")
      (node (ref "U2") (pin "3") (pinfunction "NC_3") (pintype "passive+no_connect"))
    )
    (net (code "45") (name "unconnected-(U2-NC-Pad6)") (class "Default")
      (node (ref "U2") (pin "6") (pinfunction "NC_6") (pintype "passive+no_connect"))
    )
    (net (code "46") (name "unconnected-(U2-NC-Pad7)") (class "Default")
      (node (ref "U2") (pin "7") (pinfunction "NC_7") (pintype "passive+no_connect"))
    )
    (net (code "47") (name "unconnected-(U3-PA1-Pad9)") (class "Default")
      (node (ref "U3") (pin "9") (pinfunction "PA1_9") (pintype "bidirectional"))
    )
    (net (code "48") (name "unconnected-(U3-PA5-Pad13)") (class "Default")
      (node (ref "U3") (pin "13") (pinfunction "PA5_13") (pintype "bidirectional"))
    )
    (net (code "49") (name "unconnected-(U3-PA6-Pad14)") (class "Default")
      (node (ref "U3") (pin "14") (pinfunction "PA6_14") (pintype "bidirectional"))
    )
    (net (code "50") (name "unconnected-(U3-PA7-Pad15)") (class "Default")
      (node (ref "U3") (pin "15") (pinfunction "PA7_15") (pintype "bidirectional"))
    )
    (net (code "51") (name "unconnected-(U3-PA8-Pad30)") (class "Default")
      (node (ref "U3") (pin "30") (pinfunction "PA8_30") (pintype "bidirectional"))
    )
    (net (code "52") (name "unconnected-(U3-PA9-Pad31)") (class "Default")
      (node (ref "U3") (pin "31") (pinfunction "PA9_31") (pintype "bidirectional"))
    )
    (net (code "53") (name "unconnected-(U3-PA10-Pad32)") (class "Default")
      (node (ref "U3") (pin "32") (pinfunction "PA10_32") (pintype "bidirectional"))
    )
    (net (code "54") (name "unconnected-(U3-PB1-Pad17)") (class "Default")
      (node (ref "U3") (pin "17") (pinfunction "PB1_17") (pintype "bidirectional"))
    )
    (net (code "55") (name "unconnected-(U3-PB2-Pad18)") (class "Default")
      (node (ref "U3") (pin "18") (pinfunction "PB2_18") (pintype "bidirectional"))
    )
    (net (code "56") (name "unconnected-(U3-PB3-Pad40)") (class "Default")
      (node (ref "U3") (pin "40") (pinfunction "PB3_40") (pintype "bidirectional"))
    )
    (net (code "57") (name "unconnected-(U3-PB4-Pad41)") (class "Default")
      (node (ref "U3") (pin "41") (pinfunction "PB4_41") (pintype "bidirectional"))
    )
    (net (code "58") (name "unconnected-(U3-PB5-Pad42)") (class "Default")
      (node (ref "U3") (pin "42") (pinfunction "PB5_42") (pintype "bidirectional"))
    )
    (net (code "59") (name "unconnected-(U3-PB6-Pad43)") (class "Default")
      (node (ref "U3") (pin "43") (pinfunction "PB6_43") (pintype "bidirectional"))
    )
    (net (code "60") (name "unconnected-(U3-PB9-Pad46)") (class "Default")
      (node (ref "U3") (pin "46") (pinfunction "PB9_46") (pintype "bidirectional"))
    )
    (net (code "61") (name "unconnected-(U3-PB10-Pad22)") (class "Default")
      (node (ref "U3") (pin "22") (pinfunction "PB10_22") (pintype "bidirectional"))
    )
    (net (code "62") (name "unconnected-(U3-PB11-Pad25)") (class "Default")
      (node (ref "U3") (pin "25") (pinfunction "PB11_25") (pintype "bidirectional"))
    )
    (net (code "63") (name "unconnected-(U3-PB12-Pad26)") (class "Default")
      (node (ref "U3") (pin "26") (pinfunction "PB12_26") (pintype "bidirectional"))
    )
    (net (code "64") (name "unconnected-(U3-PB15-Pad29)") (class "Default")
      (node (ref "U3") (pin "29") (pinfunction "PB15_29") (pintype "bidirectional"))
    )
    (net (code "65") (name "unconnected-(U3-PC13-Pad2)") (class "Default")
      (node (ref "U3") (pin "2") (pinfunction "PC13_2") (pintype "bidirectional"))
    )
    (net (code "66") (name "unconnected-(U3-PC14-OSC32_IN-Pad3)") (class "Default")
      (node (ref "U3") (pin "3") (pinfunction "PC14-OSC32_IN_3") (pintype "bidirectional"))
    )
    (net (code "67") (name "unconnected-(U3-PC15-OSC32_OUT-Pad4)") (class "Default")
      (node (ref "U3") (pin "4") (pinfunction "PC15-OSC32_OUT_4") (pintype "bidirectional"))
    )
    (net (code "68") (name "unconnected-(U3-PF0-OSC_IN-Pad5)") (class "Default")
      (node (ref "U3") (pin "5") (pinfunction "PF0-OSC_IN_5") (pintype "bidirectional"))
    )
    (net (code "69") (name "unconnected-(U3-PF1-OSC_OUT-Pad6)") (class "Default")
      (node (ref "U3") (pin "6") (pinfunction "PF1-OSC_OUT_6") (pintype "bidirectional"))
    )
  )
)
